# simpleCH552.net
KiCad netlist of a schematic drawn in EAGLE
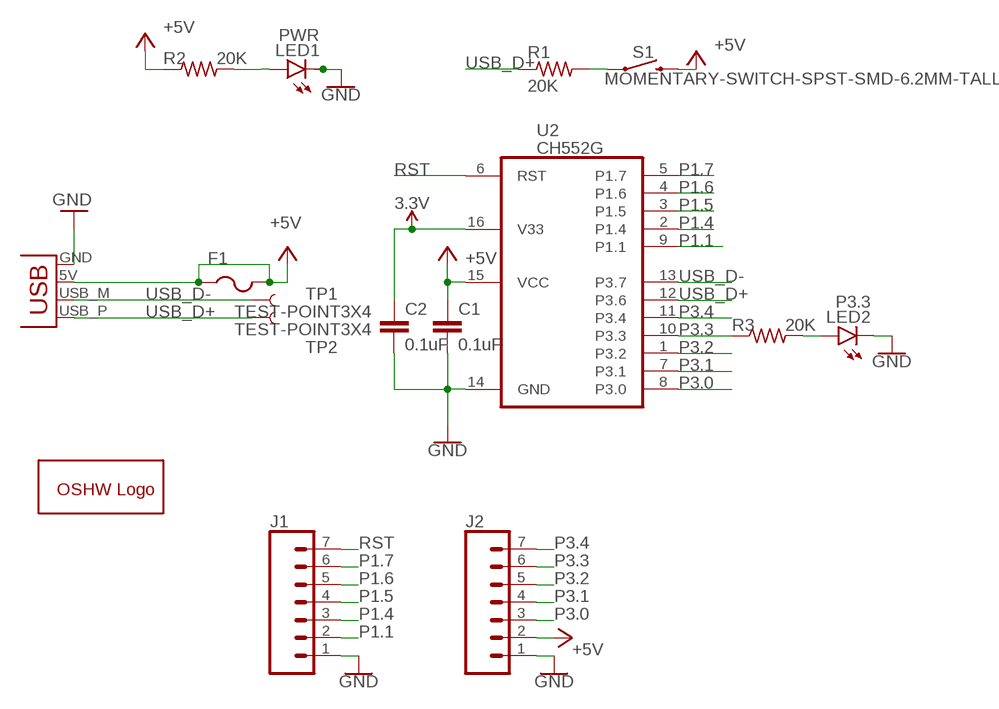
[diagram p0: schematic, sheet 1]

(export (version "E")
  (design (tool "Eeschema 10.0.6"))
  (components
    (comp (ref "C1")
      (value "0.1uF")
      (footprint "eagle-import:C0805K")
      (libsource (lib "eagle-import") (part "C-EUC0805K"))
    )
    (comp (ref "C2")
      (value "0.1uF")
      (footprint "eagle-import:C0805K")
      (libsource (lib "eagle-import") (part "C-EUC0805K"))
    )
    (comp (ref "F1")
      (value "PTCFUSE-1206")
      (footprint "eagle-import:R1206")
      (libsource (lib "eagle-import") (part "PTCFUSE-1206"))
    )
    (comp (ref "GOLD_ORB_SM1")
      (value "OSHWLOGOLOGO8MM")
      (footprint "eagle-import:OSHW_8MM")
      (libsource (lib "eagle-import") (part "OSHWLOGOLOGO8MM"))
    )
    (comp (ref "J1")
      (value "CONN_07NO_SILK")
      (footprint "eagle-import:1X07_NO_SILK")
      (libsource (lib "eagle-import") (part "CONN_07NO_SILK"))
    )
    (comp (ref "J2")
      (value "CONN_07NO_SILK")
      (footprint "eagle-import:1X07_NO_SILK")
      (libsource (lib "eagle-import") (part "CONN_07NO_SILK"))
    )
    (comp (ref "LED1")
      (value "PWR")
      (footprint "eagle-import:GHI-BASICCOMPONENTS_0805-LED")
      (libsource (lib "eagle-import") (part "GHI-BASICCOMPONENTS_LED-(INCH)-0805"))
    )
    (comp (ref "LED2")
      (value "P3.3")
      (footprint "eagle-import:GHI-BASICCOMPONENTS_0805-LED")
      (libsource (lib "eagle-import") (part "GHI-BASICCOMPONENTS_LED-(INCH)-0805"))
    )
    (comp (ref "R1")
      (value "20K")
      (footprint "eagle-import:R0805")
      (libsource (lib "eagle-import") (part "R-US_R0805"))
    )
    (comp (ref "R2")
      (value "20K")
      (footprint "eagle-import:R0805")
      (libsource (lib "eagle-import") (part "R-US_R0805"))
    )
    (comp (ref "R3")
      (value "20K")
      (footprint "eagle-import:R0805")
      (libsource (lib "eagle-import") (part "R-US_R0805"))
    )
    (comp (ref "S1")
      (value "MOMENTARY-SWITCH-SPST-SMD-6.2MM-TALL")
      (footprint "eagle-import:TACTILE_SWITCH_SMD_6.2MM_TALL")
      (libsource (lib "eagle-import") (part "MOMENTARY-SWITCH-SPST-SMD-6.2MM-TALL"))
    )
    (comp (ref "TP1")
      (value "TEST-POINT3X4")
      (footprint "eagle-import:PAD.03X.04")
      (libsource (lib "eagle-import") (part "TEST-POINT3X4"))
    )
    (comp (ref "TP2")
      (value "TEST-POINT3X4")
      (footprint "eagle-import:PAD.03X.04")
      (libsource (lib "eagle-import") (part "TEST-POINT3X4"))
    )
    (comp (ref "U2")
      (value "CH552G")
      (footprint "eagle-import:MY_IC_SO16")
      (libsource (lib "eagle-import") (part "MY_IC_CH551G_CH552GSOP-16"))
    )
    (comp (ref "X1")
      (value "USBPCB")
      (footprint "eagle-import:USB-A-PCB")
      (libsource (lib "eagle-import") (part "USBPCB"))
    )
  )
  (nets
    (net (code "1") (name "+5V") (class "Default")
      (node (ref "C1") (pin "1") (pinfunction "1_1") (pintype "passive"))
      (node (ref "F1") (pin "1") (pinfunction "1_1") (pintype "passive"))
      (node (ref "F1") (pin "2") (pinfunction "2_2") (pintype "passive"))
      (node (ref "J2") (pin "2") (pinfunction "2_2") (pintype "passive"))
      (node (ref "R2") (pin "1") (pinfunction "1_1") (pintype "passive"))
      (node (ref "S1") (pin "B2") (pinfunction "2_B2") (pintype "passive"))
      (node (ref "U2") (pin "15") (pinfunction "VCC_15") (pintype "power_in"))
      (node (ref "X1") (pin "5V") (pinfunction "VBUS_5V") (pintype "bidirectional"))
    )
    (net (code "2") (name "/P1.1") (class "Default")
      (node (ref "J1") (pin "2") (pinfunction "2_2") (pintype "passive"))
      (node (ref "U2") (pin "9") (pinfunction "P1.1_9") (pintype "bidirectional"))
    )
    (net (code "3") (name "/P1.4") (class "Default")
      (node (ref "J1") (pin "3") (pinfunction "3_3") (pintype "passive"))
      (node (ref "U2") (pin "2") (pinfunction "P1.4_2") (pintype "bidirectional"))
    )
    (net (code "4") (name "/P1.5") (class "Default")
      (node (ref "J1") (pin "4") (pinfunction "4_4") (pintype "passive"))
      (node (ref "U2") (pin "3") (pinfunction "P1.5_3") (pintype "bidirectional"))
    )
    (net (code "5") (name "/P1.6") (class "Default")
      (node (ref "J1") (pin "5") (pinfunction "5_5") (pintype "passive"))
      (node (ref "U2") (pin "4") (pinfunction "P1.6_4") (pintype "bidirectional"))
    )
    (net (code "6") (name "/P1.7") (class "Default")
      (node (ref "J1") (pin "6") (pinfunction "6_6") (pintype "passive"))
      (node (ref "U2") (pin "5") (pinfunction "P1.7_5") (pintype "bidirectional"))
    )
    (net (code "7") (name "/P3.0") (class "Default")
      (node (ref "J2") (pin "3") (pinfunction "3_3") (pintype "passive"))
      (node (ref "U2") (pin "8") (pinfunction "P3.0_8") (pintype "bidirectional"))
    )
    (net (code "8") (name "/P3.1") (class "Default")
      (node (ref "J2") (pin "4") (pinfunction "4_4") (pintype "passive"))
      (node (ref "U2") (pin "7") (pinfunction "P3.1_7") (pintype "bidirectional"))
    )
    (net (code "9") (name "/P3.2") (class "Default")
      (node (ref "J2") (pin "5") (pinfunction "5_5") (pintype "passive"))
      (node (ref "U2") (pin "1") (pinfunction "P3.2_1") (pintype "bidirectional"))
    )
    (net (code "10") (name "/P3.3") (class "Default")
      (node (ref "J2") (pin "6") (pinfunction "6_6") (pintype "passive"))
      (node (ref "R3") (pin "1") (pinfunction "1_1") (pintype "passive"))
      (node (ref "U2") (pin "10") (pinfunction "P3.3_10") (pintype "bidirectional"))
    )
    (net (code "11") (name "/P3.4") (class "Default")
      (node (ref "J2") (pin "7") (pinfunction "7_7") (pintype "passive"))
      (node (ref "U2") (pin "11") (pinfunction "P3.4_11") (pintype "bidirectional"))
    )
    (net (code "12") (name "/RST") (class "Default")
      (node (ref "J1") (pin "7") (pinfunction "7_7") (pintype "passive"))
      (node (ref "U2") (pin "6") (pinfunction "RST_6") (pintype "input"))
    )
    (net (code "13") (name "/USB_D+") (class "Default")
      (node (ref "R1") (pin "1") (pinfunction "1_1") (pintype "passive"))
      (node (ref "TP2") (pin "P$1") (pinfunction "1_P$1") (pintype "bidirectional"))
      (node (ref "U2") (pin "12") (pinfunction "P3.6_12") (pintype "bidirectional"))
      (node (ref "X1") (pin "USB_P") (pinfunction "D+_USB_P") (pintype "bidirectional"))
    )
    (net (code "14") (name "/USB_D-") (class "Default")
      (node (ref "TP1") (pin "P$1") (pinfunction "1_P$1") (pintype "bidirectional"))
      (node (ref "U2") (pin "13") (pinfunction "P3.7_13") (pintype "bidirectional"))
      (node (ref "X1") (pin "USB_M") (pinfunction "D-_USB_M") (pintype "bidirectional"))
    )
    (net (code "15") (name "3.3V") (class "Default")
      (node (ref "C2") (pin "1") (pinfunction "1_1") (pintype "passive"))
      (node (ref "U2") (pin "16") (pinfunction "V33_16") (pintype "power_in"))
    )
    (net (code "16") (name "GND") (class "Default")
      (node (ref "C1") (pin "2") (pinfunction "2_2") (pintype "passive"))
      (node (ref "C2") (pin "2") (pinfunction "2_2") (pintype "passive"))
      (node (ref "J1") (pin "1") (pinfunction "1_1") (pintype "passive"))
      (node (ref "J2") (pin "1") (pinfunction "1_1") (pintype "passive"))
      (node (ref "LED1") (pin "K") (pinfunction "K_K") (pintype "passive"))
      (node (ref "LED2") (pin "K") (pinfunction "K_K") (pintype "passive"))
      (node (ref "U2") (pin "14") (pinfunction "GND_14") (pintype "power_in"))
      (node (ref "X1") (pin "GND") (pinfunction "GND_GND") (pintype "bidirectional"))
    )
    (net (code "17") (name "Net-(LED1-PadA)") (class "Default")
      (node (ref "LED1") (pin "A") (pinfunction "A_A") (pintype "passive"))
      (node (ref "R2") (pin "2") (pinfunction "2_2") (pintype "passive"))
    )
    (net (code "18") (name "Net-(LED2-PadA)") (class "Default")
      (node (ref "LED2") (pin "A") (pinfunction "A_A") (pintype "passive"))
      (node (ref "R3") (pin "2") (pinfunction "2_2") (pintype "passive"))
    )
    (net (code "19") (name "Net-(S1-1)") (class "Default")
      (node (ref "R1") (pin "2") (pinfunction "2_2") (pintype "passive"))
      (node (ref "S1") (pin "A2") (pinfunction "1_A2") (pintype "passive"))
    )
  )
)
